# schematic.net
KiCad netlist of a schematic drawn in EAGLE
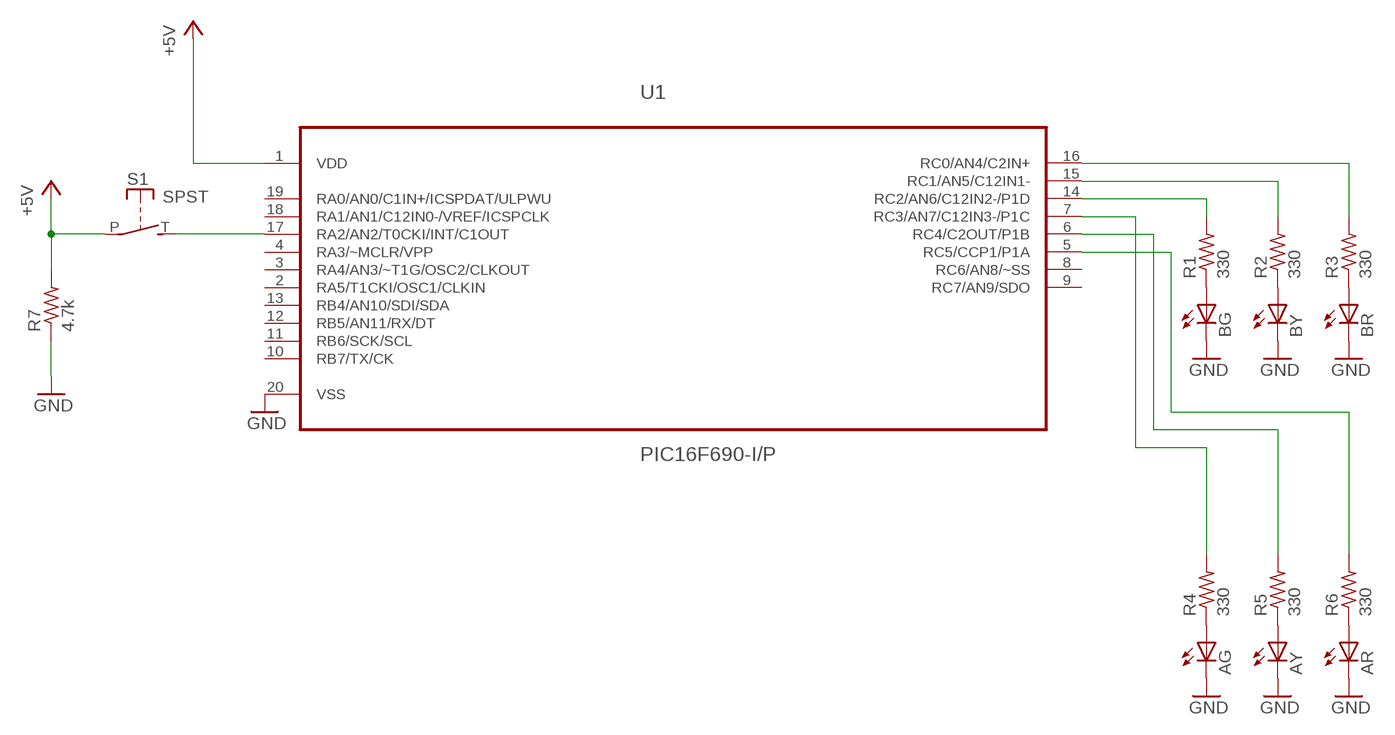
[diagram p0: schematic, sheet 1]

(export (version "E")
  (design (tool "Eeschema 10.0.6"))
  (components
    (comp (ref "AG")
      (value "LED5MM")
      (footprint "eagle-import:LED5MM")
      (libsource (lib "eagle-import") (part "LED5MM"))
    )
    (comp (ref "AR")
      (value "LED5MM")
      (footprint "eagle-import:LED5MM")
      (libsource (lib "eagle-import") (part "LED5MM"))
    )
    (comp (ref "AY")
      (value "LED5MM")
      (footprint "eagle-import:LED5MM")
      (libsource (lib "eagle-import") (part "LED5MM"))
    )
    (comp (ref "BG")
      (value "LED5MM")
      (footprint "eagle-import:LED5MM")
      (libsource (lib "eagle-import") (part "LED5MM"))
    )
    (comp (ref "BR")
      (value "LED5MM")
      (footprint "eagle-import:LED5MM")
      (libsource (lib "eagle-import") (part "LED5MM"))
    )
    (comp (ref "BY")
      (value "LED5MM")
      (footprint "eagle-import:LED5MM")
      (libsource (lib "eagle-import") (part "LED5MM"))
    )
    (comp (ref "R1")
      (value "330")
      (footprint "eagle-import:0204_5")
      (libsource (lib "eagle-import") (part "R-US_0204/5"))
    )
    (comp (ref "R2")
      (value "330")
      (footprint "eagle-import:0204_5")
      (libsource (lib "eagle-import") (part "R-US_0204/5"))
    )
    (comp (ref "R3")
      (value "330")
      (footprint "eagle-import:0204_5")
      (libsource (lib "eagle-import") (part "R-US_0204/5"))
    )
    (comp (ref "R4")
      (value "330")
      (footprint "eagle-import:0204_5")
      (libsource (lib "eagle-import") (part "R-US_0204/5"))
    )
    (comp (ref "R5")
      (value "330")
      (footprint "eagle-import:0204_5")
      (libsource (lib "eagle-import") (part "R-US_0204/5"))
    )
    (comp (ref "R6")
      (value "330")
      (footprint "eagle-import:0204_5")
      (libsource (lib "eagle-import") (part "R-US_0204/5"))
    )
    (comp (ref "R7")
      (value "4.7k")
      (footprint "eagle-import:0204_5")
      (libsource (lib "eagle-import") (part "R-US_0204/5"))
    )
    (comp (ref "S1")
      (value "SPST")
      (footprint "eagle-import:JUDCOSPST")
      (libsource (lib "eagle-import") (part "SPST"))
    )
    (comp (ref "U1")
      (value "PIC16F690-I/P")
      (footprint "eagle-import:DIP254P762X533-20")
      (fields (field (name "MF") "Microchip"))
      (libsource (lib "eagle-import") (part "PIC16F690-I/P"))
    )
  )
  (nets
    (net (code "1") (name "+5V") (class "Default")
      (node (ref "R7") (pin "2") (pinfunction "2_2") (pintype "passive"))
      (node (ref "S1") (pin "P") (pinfunction "P_P") (pintype "passive"))
      (node (ref "U1") (pin "1") (pinfunction "VDD_1") (pintype "power_in"))
    )
    (net (code "2") (name "GND") (class "Default")
      (node (ref "AG") (pin "K") (pinfunction "C_K") (pintype "passive"))
      (node (ref "AR") (pin "K") (pinfunction "C_K") (pintype "passive"))
      (node (ref "AY") (pin "K") (pinfunction "C_K") (pintype "passive"))
      (node (ref "BG") (pin "K") (pinfunction "C_K") (pintype "passive"))
      (node (ref "BR") (pin "K") (pinfunction "C_K") (pintype "passive"))
      (node (ref "BY") (pin "K") (pinfunction "C_K") (pintype "passive"))
      (node (ref "R7") (pin "1") (pinfunction "1_1") (pintype "passive"))
      (node (ref "U1") (pin "20") (pinfunction "VSS_20") (pintype "power_in"))
    )
    (net (code "3") (name "Net-(AG-PadA)") (class "Default")
      (node (ref "AG") (pin "A") (pinfunction "A_A") (pintype "passive"))
      (node (ref "R4") (pin "1") (pinfunction "1_1") (pintype "passive"))
    )
    (net (code "4") (name "Net-(AR-PadA)") (class "Default")
      (node (ref "AR") (pin "A") (pinfunction "A_A") (pintype "passive"))
      (node (ref "R6") (pin "1") (pinfunction "1_1") (pintype "passive"))
    )
    (net (code "5") (name "Net-(AY-PadA)") (class "Default")
      (node (ref "AY") (pin "A") (pinfunction "A_A") (pintype "passive"))
      (node (ref "R5") (pin "1") (pinfunction "1_1") (pintype "passive"))
    )
    (net (code "6") (name "Net-(BG-PadA)") (class "Default")
      (node (ref "BG") (pin "A") (pinfunction "A_A") (pintype "passive"))
      (node (ref "R1") (pin "1") (pinfunction "1_1") (pintype "passive"))
    )
    (net (code "7") (name "Net-(BR-PadA)") (class "Default")
      (node (ref "BR") (pin "A") (pinfunction "A_A") (pintype "passive"))
      (node (ref "R3") (pin "1") (pinfunction "1_1") (pintype "passive"))
    )
    (net (code "8") (name "Net-(BY-PadA)") (class "Default")
      (node (ref "BY") (pin "A") (pinfunction "A_A") (pintype "passive"))
      (node (ref "R2") (pin "1") (pinfunction "1_1") (pintype "passive"))
    )
    (net (code "9") (name "Net-(S1-S)") (class "Default")
      (node (ref "S1") (pin "T") (pinfunction "S_T") (pintype "passive"))
      (node (ref "U1") (pin "17") (pinfunction "RA2/AN2/T0CKI/INT/C1OUT_17") (pintype "bidirectional"))
    )
    (net (code "10") (name "Net-(U1-RC0{slash}AN4{slash}C2IN+)") (class "Default")
      (node (ref "R3") (pin "2") (pinfunction "2_2") (pintype "passive"))
      (node (ref "U1") (pin "16") (pinfunction "RC0/AN4/C2IN+_16") (pintype "bidirectional"))
    )
    (net (code "11") (name "Net-(U1-RC1{slash}AN5{slash}C12IN1-)") (class "Default")
      (node (ref "R2") (pin "2") (pinfunction "2_2") (pintype "passive"))
      (node (ref "U1") (pin "15") (pinfunction "RC1/AN5/C12IN1-_15") (pintype "bidirectional"))
    )
    (net (code "12") (name "Net-(U1-RC2{slash}AN6{slash}C12IN2-{slash}P1D)") (class "Default")
      (node (ref "R1") (pin "2") (pinfunction "2_2") (pintype "passive"))
      (node (ref "U1") (pin "14") (pinfunction "RC2/AN6/C12IN2-/P1D_14") (pintype "bidirectional"))
    )
    (net (code "13") (name "Net-(U1-RC3{slash}AN7{slash}C12IN3-{slash}P1C)") (class "Default")
      (node (ref "R4") (pin "2") (pinfunction "2_2") (pintype "passive"))
      (node (ref "U1") (pin "7") (pinfunction "RC3/AN7/C12IN3-/P1C_7") (pintype "bidirectional"))
    )
    (net (code "14") (name "Net-(U1-RC4{slash}C2OUT{slash}P1B)") (class "Default")
      (node (ref "R5") (pin "2") (pinfunction "2_2") (pintype "passive"))
      (node (ref "U1") (pin "6") (pinfunction "RC4/C2OUT/P1B_6") (pintype "bidirectional"))
    )
    (net (code "15") (name "Net-(U1-RC5{slash}CCP1{slash}P1A)") (class "Default")
      (node (ref "R6") (pin "2") (pinfunction "2_2") (pintype "passive"))
      (node (ref "U1") (pin "5") (pinfunction "RC5/CCP1/P1A_5") (pintype "bidirectional"))
    )
    (net (code "16") (name "unconnected-(U1-RA0{slash}AN0{slash}C1IN+{slash}ICSPDAT{slash}ULPWU-Pad19)") (class "Default")
      (node (ref "U1") (pin "19") (pinfunction "RA0/AN0/C1IN+/ICSPDAT/ULPWU_19") (pintype "bidirectional"))
    )
    (net (code "17") (name "unconnected-(U1-RA1{slash}AN1{slash}C12IN0-{slash}VREF{slash}ICSPCLK-Pad18)") (class "Default")
      (node (ref "U1") (pin "18") (pinfunction "RA1/AN1/C12IN0-/VREF/ICSPCLK_18") (pintype "bidirectional"))
    )
    (net (code "18") (name "unconnected-(U1-RA3{slash}~{MCLR{slash}VPP}-Pad4)") (class "Default")
      (node (ref "U1") (pin "4") (pinfunction "RA3/~{MCLR/VPP}_4") (pintype "input"))
    )
    (net (code "19") (name "unconnected-(U1-RA4{slash}AN3{slash}~{T1G{slash}OSC2{slash}CLKOUT}-Pad3)") (class "Default")
      (node (ref "U1") (pin "3") (pinfunction "RA4/AN3/~{T1G/OSC2/CLKOUT}_3") (pintype "bidirectional"))
    )
    (net (code "20") (name "unconnected-(U1-RA5{slash}T1CKI{slash}OSC1{slash}CLKIN-Pad2)") (class "Default")
      (node (ref "U1") (pin "2") (pinfunction "RA5/T1CKI/OSC1/CLKIN_2") (pintype "bidirectional"))
    )
    (net (code "21") (name "unconnected-(U1-RB4{slash}AN10{slash}SDI{slash}SDA-Pad13)") (class "Default")
      (node (ref "U1") (pin "13") (pinfunction "RB4/AN10/SDI/SDA_13") (pintype "bidirectional"))
    )
    (net (code "22") (name "unconnected-(U1-RB5{slash}AN11{slash}RX{slash}DT-Pad12)") (class "Default")
      (node (ref "U1") (pin "12") (pinfunction "RB5/AN11/RX/DT_12") (pintype "bidirectional"))
    )
    (net (code "23") (name "unconnected-(U1-RB6{slash}SCK{slash}SCL-Pad11)") (class "Default")
      (node (ref "U1") (pin "11") (pinfunction "RB6/SCK/SCL_11") (pintype "bidirectional"))
    )
    (net (code "24") (name "unconnected-(U1-RB7{slash}TX{slash}CK-Pad10)") (class "Default")
      (node (ref "U1") (pin "10") (pinfunction "RB7/TX/CK_10") (pintype "bidirectional"))
    )
    (net (code "25") (name "unconnected-(U1-RC6{slash}AN8{slash}~{SS}-Pad8)") (class "Default")
      (node (ref "U1") (pin "8") (pinfunction "RC6/AN8/~{SS}_8") (pintype "bidirectional"))
    )
    (net (code "26") (name "unconnected-(U1-RC7{slash}AN9{slash}SDO-Pad9)") (class "Default")
      (node (ref "U1") (pin "9") (pinfunction "RC7/AN9/SDO_9") (pintype "bidirectional"))
    )
  )
)
